# SCH_TimeCortex_2026-06-23.net
KiCad netlist of a schematic drawn in EasyEDA
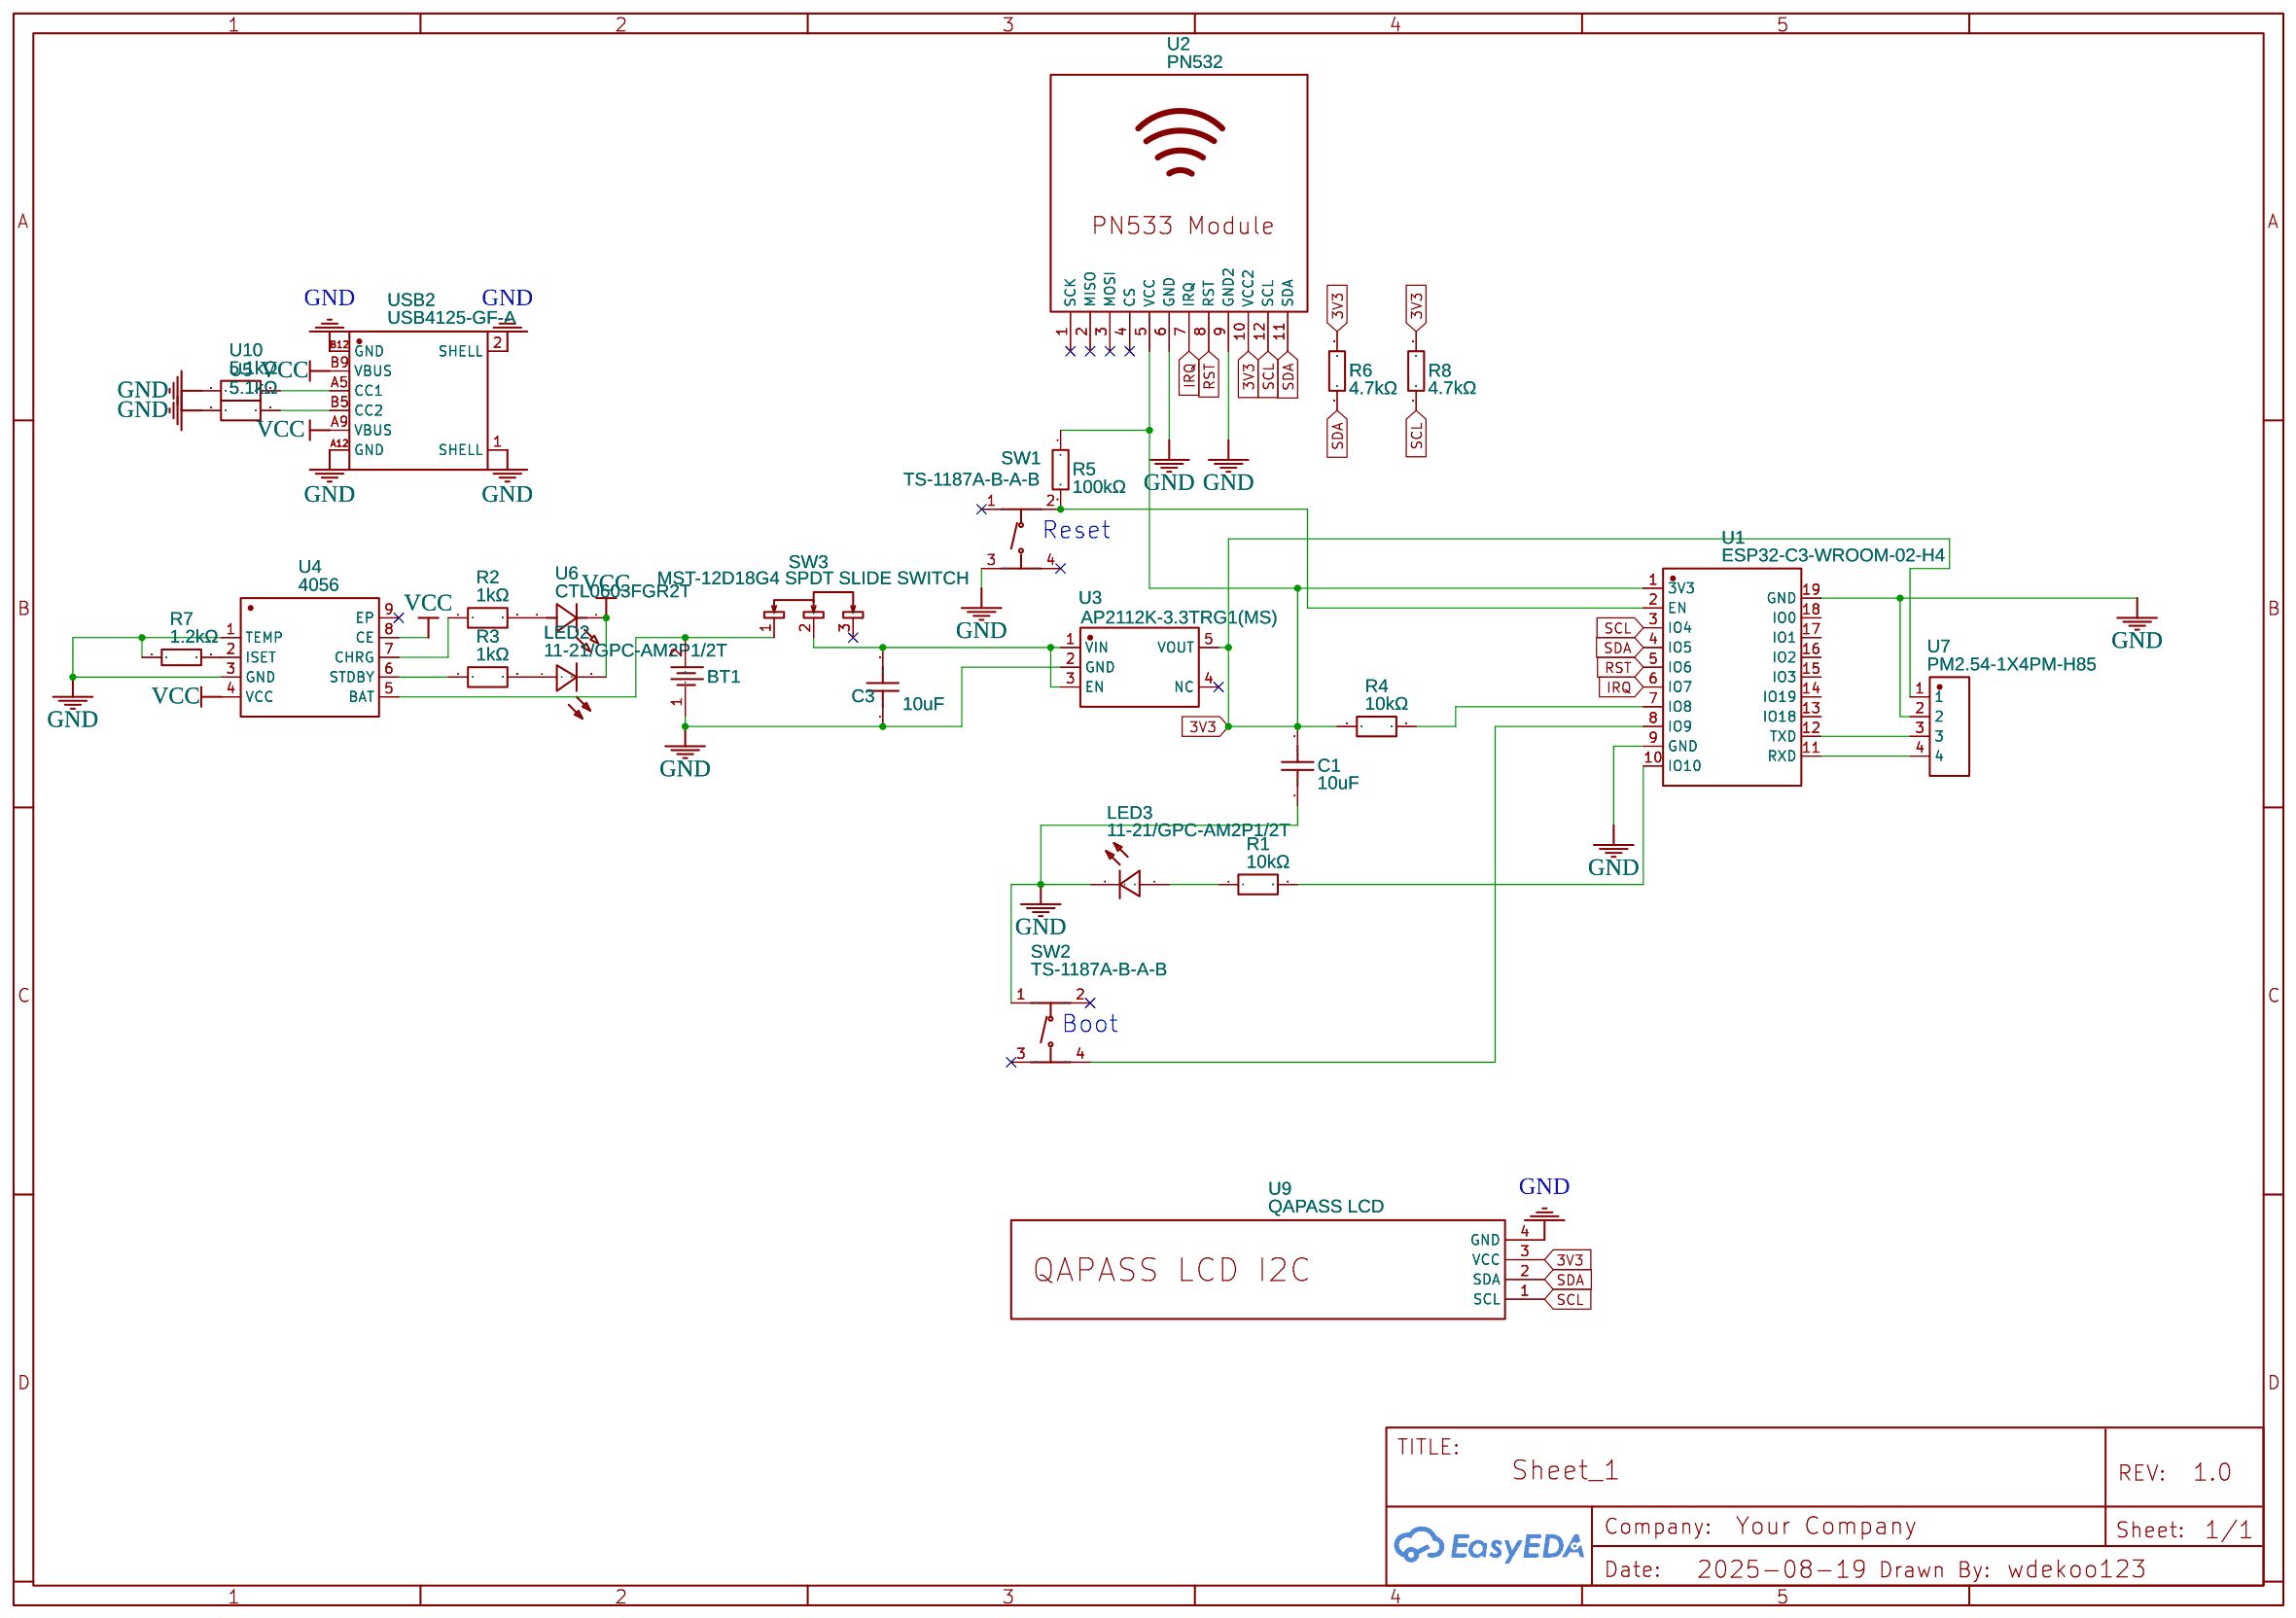
[diagram p0: schematic sheet]

(export (version "E")
  (design (tool "Eeschema 10.0.6"))
  (components
    (comp (ref "BT1")
      (value "BH-18650-1")
      (fields (field (name "Manufacturer") "HanElectricity(瀚源)"))
      (libsource (lib "") (part "BH-18650-1"))
    )
    (comp (ref "C1")
      (value "10uF")
      (fields
        (field (name "Manufacturer Part") "CL21A106KAYNNNE")
        (field (name "Manufacturer") "SAMSUNG(三星)")
      )
      (libsource (lib "") (part "CL21A106KAYNNNE"))
    )
    (comp (ref "C3")
      (value "10uF")
      (fields
        (field (name "Manufacturer Part") "CL21A106KAYNNNE")
        (field (name "Manufacturer") "SAMSUNG(三星)")
      )
      (libsource (lib "") (part "CL21A106KAYNNNE"))
    )
    (comp (ref "LED2")
      (value "11-21/GPC-AM2P1/2T")
      (fields (field (name "Manufacturer") "EVERLIGHT(亿光)"))
      (libsource (lib "") (part "11-21/GPC-AM2P1/2T"))
    )
    (comp (ref "LED3")
      (value "11-21/GPC-AM2P1/2T")
      (fields (field (name "Manufacturer") "EVERLIGHT(亿光)"))
      (libsource (lib "") (part "11-21/GPC-AM2P1/2T_1"))
    )
    (comp (ref "R1")
      (value "10kΩ")
      (fields (field (name "Manufacturer Part") "AC0402FR-1310KL") (field (name "Manufacturer") "YAGEO(国巨)"))
      (libsource (lib "") (part "AC0402FR-1310KL"))
    )
    (comp (ref "R2")
      (value "1kΩ")
      (fields
        (field (name "Manufacturer Part") "0805W8D1001T5E")
        (field (name "Manufacturer") "UNI-ROYAL(厚声)")
      )
      (libsource (lib "") (part "0805W8D1001T5E"))
    )
    (comp (ref "R3")
      (value "1kΩ")
      (fields
        (field (name "Manufacturer Part") "0805W8D1001T5E")
        (field (name "Manufacturer") "UNI-ROYAL(厚声)")
      )
      (libsource (lib "") (part "0805W8D1001T5E"))
    )
    (comp (ref "R4")
      (value "10kΩ")
      (fields (field (name "Manufacturer Part") "AC0402FR-1310KL") (field (name "Manufacturer") "YAGEO(国巨)"))
      (libsource (lib "") (part "AC0402FR-1310KL"))
    )
    (comp (ref "R5")
      (value "100kΩ")
      (fields (field (name "Manufacturer Part") "AR05DTDW1003") (field (name "Manufacturer") "Viking(光颉)"))
      (libsource (lib "") (part "AR05DTDW1003"))
    )
    (comp (ref "R6")
      (value "4.7kΩ")
      (fields
        (field (name "Manufacturer Part") "0402WGF4701TCE")
        (field (name "Manufacturer") "UNI-ROYAL(厚声)")
      )
      (libsource (lib "") (part "0402WGF4701TCE"))
    )
    (comp (ref "R7")
      (value "1.2kΩ")
      (fields
        (field (name "Manufacturer Part") "1206W4F1201T5E")
        (field (name "Manufacturer") "UNI-ROYAL(厚声)")
      )
      (libsource (lib "") (part "1206W4F1201T5E"))
    )
    (comp (ref "R8")
      (value "4.7kΩ")
      (fields
        (field (name "Manufacturer Part") "0402WGF4701TCE")
        (field (name "Manufacturer") "UNI-ROYAL(厚声)")
      )
      (libsource (lib "") (part "0402WGF4701TCE"))
    )
    (comp (ref "SW1")
      (value "TS-1187A-B-A-B")
      (fields (field (name "Manufacturer") "XKB Connection(中国星坤)"))
      (libsource (lib "") (part "TS-1187A-B-A-B"))
    )
    (comp (ref "SW2")
      (value "TS-1187A-B-A-B")
      (fields (field (name "Manufacturer") "XKB Connection(中国星坤)"))
      (libsource (lib "") (part "TS-1187A-B-A-B"))
    )
    (comp (ref "SW3")
      (value "MST-12D18G4 SPDT SLIDE SWITCH")
      (fields
        (field (name "Manufacturer Part") "MST-12D18G4 SPDT Slide Switch")
        (field (name "Manufacturer") "SHOU HAN(首韩)")
      )
      (libsource (lib "") (part "MST-12D18G4 SPDT SLIDE SWITCH"))
    )
    (comp (ref "U1")
      (value "ESP32-C3-WROOM-02-H4")
      (fields (field (name "Manufacturer") "ESPRESSIF(乐鑫)"))
      (libsource (lib "") (part "ESP32-C3-WROOM-02-H4"))
    )
    (comp (ref "U2")
      (value "PN532")
      (fields (field (name "Manufacturer Part") "Header2.54mm 1*8P") (field (name "Manufacturer") "ReliaPro"))
      (libsource (lib "") (part "PN532"))
    )
    (comp (ref "U3")
      (value "AP2112K-3.3TRG1(MS)")
      (fields (field (name "Manufacturer") "MSKSEMI(美森科)"))
      (libsource (lib "") (part "AP2112K-3.3TRG1(MS)"))
    )
    (comp (ref "U4")
      (value "4056")
      (fields (field (name "Manufacturer") "RONGHE(融和)"))
      (libsource (lib "") (part "4056"))
    )
    (comp (ref "U5")
      (value "5.1kΩ")
      (fields (field (name "Manufacturer Part") "FRC0603J512 TS") (field (name "Manufacturer") "FOJAN(富捷)"))
      (libsource (lib "") (part "FRC0603J512 TS"))
    )
    (comp (ref "U6")
      (value "CTL0603FGR2T")
      (fields (field (name "Manufacturer") "Venkel"))
      (libsource (lib "") (part "CTL0603FGR2T"))
    )
    (comp (ref "U7")
      (value "PM2.54-1X4PM-H85")
      (fields (field (name "Manufacturer") "JXTCONN(聚兴泰)"))
      (libsource (lib "") (part "PM2.54-1X4PM-H85"))
    )
    (comp (ref "U9") (value "QAPASS LCD") (libsource (lib "") (part "QAPASS LCD")))
    (comp (ref "U10")
      (value "5.1kΩ")
      (fields (field (name "Manufacturer Part") "FRC0603J512 TS") (field (name "Manufacturer") "FOJAN(富捷)"))
      (libsource (lib "") (part "FRC0603J512 TS"))
    )
    (comp (ref "USB2")
      (value "USB4125-GF-A")
      (fields (field (name "Manufacturer") "GCT"))
      (libsource (lib "") (part "USB4125-GF-A"))
    )
  )
  (nets
    (net (code "1") (name "3V3") (class "Default")
      (node (ref "C1") (pin "2") (pinfunction "2_2") (pintype "unspecified"))
      (node (ref "R4") (pin "1") (pinfunction "1_1") (pintype "unspecified"))
      (node (ref "R5") (pin "1") (pinfunction "1_1") (pintype "unspecified"))
      (node (ref "R6") (pin "2") (pinfunction "2_2") (pintype "input"))
      (node (ref "R8") (pin "2") (pinfunction "2_2") (pintype "input"))
      (node (ref "U1") (pin "1") (pinfunction "3V3_1") (pintype "unspecified"))
      (node (ref "U2") (pin "10") (pinfunction "VCC2_10") (pintype "unspecified"))
      (node (ref "U2") (pin "5") (pinfunction "VCC_5") (pintype "unspecified"))
      (node (ref "U3") (pin "5") (pinfunction "VOUT_5") (pintype "unspecified"))
      (node (ref "U7") (pin "1") (pinfunction "1_1") (pintype "unspecified"))
      (node (ref "U9") (pin "3") (pinfunction "VCC_3") (pintype "unspecified"))
    )
    (net (code "2") (name "GND") (class "Default")
      (node (ref "BT1") (pin "1") (pinfunction "1_1") (pintype "input"))
      (node (ref "C1") (pin "1") (pinfunction "1_1") (pintype "unspecified"))
      (node (ref "C3") (pin "1") (pinfunction "1_1") (pintype "unspecified"))
      (node (ref "LED3") (pin "2") (pinfunction "K_2") (pintype "unspecified"))
      (node (ref "R7") (pin "1") (pinfunction "1_1") (pintype "input"))
      (node (ref "SW1") (pin "3") (pinfunction "C_3") (pintype "unspecified"))
      (node (ref "SW2") (pin "1") (pinfunction "A_1") (pintype "unspecified"))
      (node (ref "U1") (pin "19") (pinfunction "GND_19") (pintype "unspecified"))
      (node (ref "U1") (pin "9") (pinfunction "GND_9") (pintype "unspecified"))
      (node (ref "U10") (pin "1") (pinfunction "1_1") (pintype "unspecified"))
      (node (ref "U2") (pin "6") (pinfunction "GND_6") (pintype "unspecified"))
      (node (ref "U2") (pin "9") (pinfunction "GND2_9") (pintype "unspecified"))
      (node (ref "U3") (pin "2") (pinfunction "GND_2") (pintype "unspecified"))
      (node (ref "U4") (pin "1") (pinfunction "TEMP_1") (pintype "unspecified"))
      (node (ref "U4") (pin "3") (pinfunction "GND_3") (pintype "unspecified"))
      (node (ref "U5") (pin "1") (pinfunction "1_1") (pintype "unspecified"))
      (node (ref "U7") (pin "2") (pinfunction "2_2") (pintype "unspecified"))
      (node (ref "U9") (pin "4") (pinfunction "GND_4") (pintype "unspecified"))
      (node (ref "USB2") (pin "1") (pinfunction "SHELL_1") (pintype "unspecified"))
      (node (ref "USB2") (pin "2") (pinfunction "SHELL_2") (pintype "unspecified"))
      (node (ref "USB2") (pin "A12") (pinfunction "GND_A12") (pintype "unspecified"))
      (node (ref "USB2") (pin "B12") (pinfunction "GND_B12") (pintype "unspecified"))
    )
    (net (code "3") (name "IRQ") (class "Default")
      (node (ref "U1") (pin "6") (pinfunction "IO7_6") (pintype "unspecified"))
      (node (ref "U2") (pin "7") (pinfunction "IRQ_7") (pintype "unspecified"))
    )
    (net (code "4") (name "Net-(LED2-A)") (class "Default")
      (node (ref "LED2") (pin "1") (pinfunction "A_1") (pintype "unspecified"))
      (node (ref "R3") (pin "2") (pinfunction "2_2") (pintype "unspecified"))
    )
    (net (code "5") (name "Net-(LED3-A)") (class "Default")
      (node (ref "LED3") (pin "1") (pinfunction "A_1") (pintype "unspecified"))
      (node (ref "R1") (pin "1") (pinfunction "1_1") (pintype "unspecified"))
    )
    (net (code "6") (name "Net-(SW1-B)") (class "Default")
      (node (ref "R5") (pin "2") (pinfunction "2_2") (pintype "unspecified"))
      (node (ref "SW1") (pin "2") (pinfunction "B_2") (pintype "unspecified"))
      (node (ref "U1") (pin "2") (pinfunction "EN_2") (pintype "unspecified"))
    )
    (net (code "7") (name "Net-(SW2-D)") (class "Default")
      (node (ref "SW2") (pin "4") (pinfunction "D_4") (pintype "unspecified"))
      (node (ref "U1") (pin "8") (pinfunction "IO9_8") (pintype "unspecified"))
    )
    (net (code "8") (name "Net-(U1-IO8)") (class "Default")
      (node (ref "R4") (pin "2") (pinfunction "2_2") (pintype "unspecified"))
      (node (ref "U1") (pin "7") (pinfunction "IO8_7") (pintype "unspecified"))
    )
    (net (code "9") (name "Net-(U1-IO10)") (class "Default")
      (node (ref "R1") (pin "2") (pinfunction "2_2") (pintype "unspecified"))
      (node (ref "U1") (pin "10") (pinfunction "IO10_10") (pintype "unspecified"))
    )
    (net (code "10") (name "Net-(U1-RXD)") (class "Default")
      (node (ref "U1") (pin "11") (pinfunction "RXD_11") (pintype "unspecified"))
      (node (ref "U7") (pin "4") (pinfunction "4_4") (pintype "unspecified"))
    )
    (net (code "11") (name "Net-(U1-TXD)") (class "Default")
      (node (ref "U1") (pin "12") (pinfunction "TXD_12") (pintype "unspecified"))
      (node (ref "U7") (pin "3") (pinfunction "3_3") (pintype "unspecified"))
    )
    (net (code "12") (name "Net-(U3-EN)") (class "Default")
      (node (ref "C3") (pin "2") (pinfunction "2_2") (pintype "unspecified"))
      (node (ref "SW3") (pin "2") (pinfunction "2_2") (pintype "unspecified"))
      (node (ref "U3") (pin "1") (pinfunction "VIN_1") (pintype "unspecified"))
      (node (ref "U3") (pin "3") (pinfunction "EN_3") (pintype "unspecified"))
    )
    (net (code "13") (name "Net-(U4-BAT)") (class "Default")
      (node (ref "BT1") (pin "2") (pinfunction "2_2") (pintype "input"))
      (node (ref "SW3") (pin "1") (pinfunction "1_1") (pintype "unspecified"))
      (node (ref "U4") (pin "5") (pinfunction "BAT_5") (pintype "unspecified"))
    )
    (net (code "14") (name "Net-(U4-CHRG)") (class "Default")
      (node (ref "R2") (pin "1") (pinfunction "1_1") (pintype "unspecified"))
      (node (ref "U4") (pin "7") (pinfunction "CHRG_7") (pintype "unspecified"))
    )
    (net (code "15") (name "Net-(U4-ISET)") (class "Default")
      (node (ref "R7") (pin "2") (pinfunction "2_2") (pintype "input"))
      (node (ref "U4") (pin "2") (pinfunction "ISET_2") (pintype "unspecified"))
    )
    (net (code "16") (name "Net-(U4-STDBY)") (class "Default")
      (node (ref "R3") (pin "1") (pinfunction "1_1") (pintype "unspecified"))
      (node (ref "U4") (pin "6") (pinfunction "STDBY_6") (pintype "unspecified"))
    )
    (net (code "17") (name "Net-(U6-A)") (class "Default")
      (node (ref "R2") (pin "2") (pinfunction "2_2") (pintype "unspecified"))
      (node (ref "U6") (pin "2") (pinfunction "A_2") (pintype "unspecified"))
    )
    (net (code "18") (name "Net-(USB2-CC1)") (class "Default")
      (node (ref "U10") (pin "2") (pinfunction "2_2") (pintype "unspecified"))
      (node (ref "USB2") (pin "A5") (pinfunction "CC1_A5") (pintype "unspecified"))
    )
    (net (code "19") (name "Net-(USB2-CC2)") (class "Default")
      (node (ref "U5") (pin "2") (pinfunction "2_2") (pintype "unspecified"))
      (node (ref "USB2") (pin "B5") (pinfunction "CC2_B5") (pintype "unspecified"))
    )
    (net (code "20") (name "RST") (class "Default")
      (node (ref "U1") (pin "5") (pinfunction "IO6_5") (pintype "unspecified"))
      (node (ref "U2") (pin "8") (pinfunction "RST_8") (pintype "unspecified"))
    )
    (net (code "21") (name "SCL") (class "Default")
      (node (ref "R8") (pin "1") (pinfunction "1_1") (pintype "input"))
      (node (ref "U1") (pin "3") (pinfunction "IO4_3") (pintype "unspecified"))
      (node (ref "U2") (pin "12") (pinfunction "SCL_12") (pintype "unspecified"))
      (node (ref "U9") (pin "1") (pinfunction "SCL_1") (pintype "unspecified"))
    )
    (net (code "22") (name "SDA") (class "Default")
      (node (ref "R6") (pin "1") (pinfunction "1_1") (pintype "input"))
      (node (ref "U1") (pin "4") (pinfunction "IO5_4") (pintype "unspecified"))
      (node (ref "U2") (pin "11") (pinfunction "SDA_11") (pintype "unspecified"))
      (node (ref "U9") (pin "2") (pinfunction "SDA_2") (pintype "unspecified"))
    )
    (net (code "23") (name "VCC") (class "Default")
      (node (ref "LED2") (pin "2") (pinfunction "K_2") (pintype "unspecified"))
      (node (ref "U4") (pin "4") (pinfunction "VCC_4") (pintype "unspecified"))
      (node (ref "U4") (pin "8") (pinfunction "CE_8") (pintype "unspecified"))
      (node (ref "U6") (pin "1") (pinfunction "K_1") (pintype "unspecified"))
      (node (ref "USB2") (pin "A9") (pinfunction "VBUS_A9") (pintype "unspecified"))
      (node (ref "USB2") (pin "B9") (pinfunction "VBUS_B9") (pintype "unspecified"))
    )
    (net (code "24") (name "unconnected-(SW1-A-Pad1)") (class "Default")
      (node (ref "SW1") (pin "1") (pinfunction "A_1") (pintype "unspecified+no_connect"))
    )
    (net (code "25") (name "unconnected-(SW1-D-Pad4)") (class "Default")
      (node (ref "SW1") (pin "4") (pinfunction "D_4") (pintype "unspecified+no_connect"))
    )
    (net (code "26") (name "unconnected-(SW2-B-Pad2)") (class "Default")
      (node (ref "SW2") (pin "2") (pinfunction "B_2") (pintype "unspecified+no_connect"))
    )
    (net (code "27") (name "unconnected-(SW2-C-Pad3)") (class "Default")
      (node (ref "SW2") (pin "3") (pinfunction "C_3") (pintype "unspecified+no_connect"))
    )
    (net (code "28") (name "unconnected-(SW3-Pad3)") (class "Default")
      (node (ref "SW3") (pin "3") (pinfunction "3_3") (pintype "unspecified+no_connect"))
    )
    (net (code "29") (name "unconnected-(U1-IO0-Pad18)") (class "Default")
      (node (ref "U1") (pin "18") (pinfunction "IO0_18") (pintype "unspecified"))
    )
    (net (code "30") (name "unconnected-(U1-IO1-Pad17)") (class "Default")
      (node (ref "U1") (pin "17") (pinfunction "IO1_17") (pintype "unspecified"))
    )
    (net (code "31") (name "unconnected-(U1-IO2-Pad16)") (class "Default")
      (node (ref "U1") (pin "16") (pinfunction "IO2_16") (pintype "unspecified"))
    )
    (net (code "32") (name "unconnected-(U1-IO3-Pad15)") (class "Default")
      (node (ref "U1") (pin "15") (pinfunction "IO3_15") (pintype "unspecified"))
    )
    (net (code "33") (name "unconnected-(U1-IO18-Pad13)") (class "Default")
      (node (ref "U1") (pin "13") (pinfunction "IO18_13") (pintype "unspecified"))
    )
    (net (code "34") (name "unconnected-(U1-IO19-Pad14)") (class "Default")
      (node (ref "U1") (pin "14") (pinfunction "IO19_14") (pintype "unspecified"))
    )
    (net (code "35") (name "unconnected-(U2-CS-Pad4)") (class "Default")
      (node (ref "U2") (pin "4") (pinfunction "CS_4") (pintype "unspecified+no_connect"))
    )
    (net (code "36") (name "unconnected-(U2-MISO-Pad2)") (class "Default")
      (node (ref "U2") (pin "2") (pinfunction "MISO_2") (pintype "unspecified+no_connect"))
    )
    (net (code "37") (name "unconnected-(U2-MOSI-Pad3)") (class "Default")
      (node (ref "U2") (pin "3") (pinfunction "MOSI_3") (pintype "unspecified+no_connect"))
    )
    (net (code "38") (name "unconnected-(U2-SCK-Pad1)") (class "Default")
      (node (ref "U2") (pin "1") (pinfunction "SCK_1") (pintype "unspecified+no_connect"))
    )
    (net (code "39") (name "unconnected-(U3-NC-Pad4)") (class "Default")
      (node (ref "U3") (pin "4") (pinfunction "NC_4") (pintype "unspecified+no_connect"))
    )
    (net (code "40") (name "unconnected-(U4-EP-Pad9)") (class "Default")
      (node (ref "U4") (pin "9") (pinfunction "EP_9") (pintype "unspecified+no_connect"))
    )
  )
)
